# SQUID_Channel_DACS.net
KiCad netlist of a schematic drawn in Altium Designer
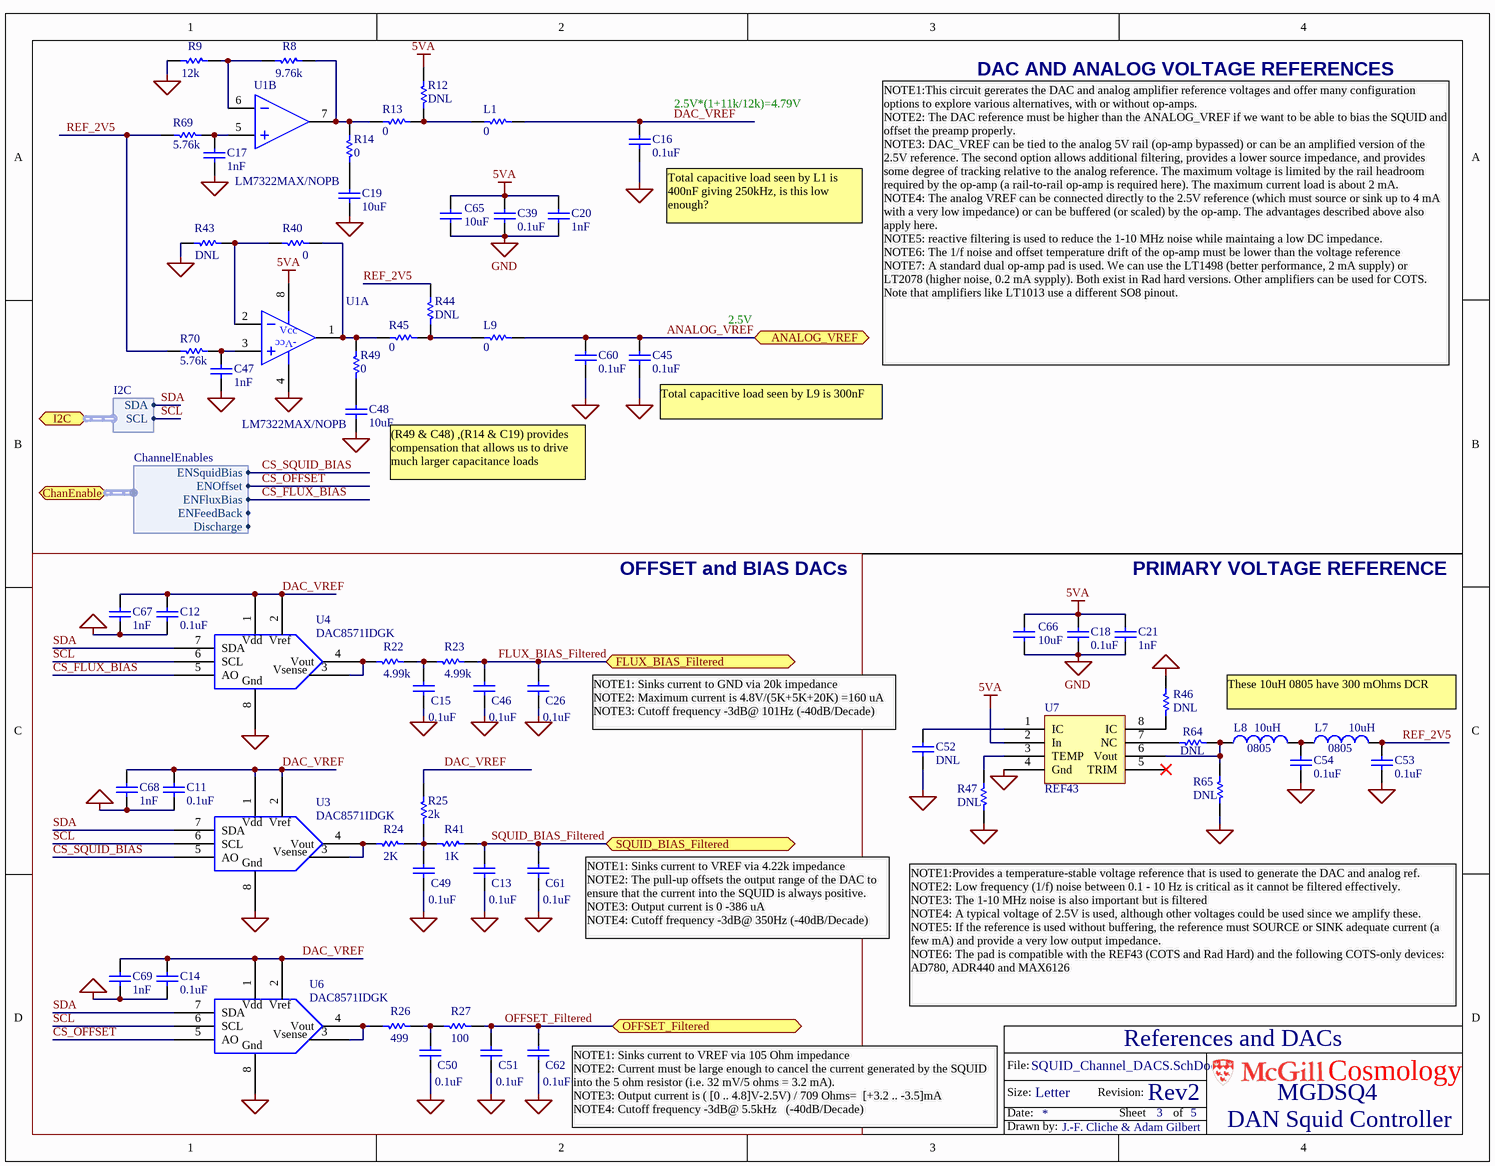
[diagram p0: SQUID_Channel_DACS.SchDoc]

(export (version "E")
  (design (tool "Eeschema 10.0.6"))
  (components
    (comp (ref "C11")
      (value "0.1uF")
      (footprint "0603")
      (description "Capacitor, Ceramic, 0603")
      (fields (field (name "MANUFACTURER") "Generic"))
      (libsource (lib "MiniSquidCtrl") (part "Cap0603"))
    )
    (comp (ref "C12")
      (value "0.1uF")
      (footprint "0603")
      (description "Capacitor, Ceramic, 0603")
      (fields (field (name "MANUFACTURER") "Generic"))
      (libsource (lib "MiniSquidCtrl") (part "Cap0603"))
    )
    (comp (ref "C13")
      (value "0.1uF")
      (footprint "0603")
      (description "Capacitor, Ceramic, 0603")
      (fields (field (name "MANUFACTURER") "Generic"))
      (libsource (lib "MiniSquidCtrl") (part "Cap0603"))
    )
    (comp (ref "C14")
      (value "0.1uF")
      (footprint "0603")
      (description "Capacitor, Ceramic, 0603")
      (fields (field (name "MANUFACTURER") "Generic"))
      (libsource (lib "MiniSquidCtrl") (part "Cap0603"))
    )
    (comp (ref "C15")
      (value "0.1uF")
      (footprint "0603")
      (description "Capacitor, Ceramic, 0603")
      (fields (field (name "MANUFACTURER") "Generic"))
      (libsource (lib "MiniSquidCtrl") (part "Cap0603"))
    )
    (comp (ref "C16")
      (value "0.1uF")
      (footprint "0603")
      (description "Capacitor, Ceramic, 0603")
      (fields (field (name "MANUFACTURER") "Generic"))
      (libsource (lib "MiniSquidCtrl") (part "Cap0603"))
    )
    (comp (ref "C17")
      (value "1nF")
      (footprint "0603")
      (description "Capacitor, Ceramic, 0603")
      (fields (field (name "MANUFACTURER") "Generic"))
      (libsource (lib "MiniSquidCtrl") (part "Cap0603"))
    )
    (comp (ref "C18")
      (value "0.1uF")
      (footprint "0603")
      (description "Capacitor, Ceramic, 0603")
      (fields (field (name "MANUFACTURER") "Generic"))
      (libsource (lib "MiniSquidCtrl") (part "Cap0603"))
    )
    (comp (ref "C19")
      (value "10uF")
      (footprint "0603")
      (description "Capacitor, Ceramic, 0603")
      (fields (field (name "MANUFACTURER") "Generic"))
      (libsource (lib "MiniSquidCtrl") (part "Cap0603"))
    )
    (comp (ref "C20")
      (value "1nF")
      (footprint "0603")
      (description "Capacitor, Ceramic, 0603")
      (fields (field (name "MANUFACTURER") "Generic"))
      (libsource (lib "MiniSquidCtrl") (part "Cap0603"))
    )
    (comp (ref "C21")
      (value "1nF")
      (footprint "0603")
      (description "Capacitor, Ceramic, 0603")
      (fields (field (name "MANUFACTURER") "Generic"))
      (libsource (lib "MiniSquidCtrl") (part "Cap0603"))
    )
    (comp (ref "C26")
      (value "0.1uF")
      (footprint "0603")
      (description "Capacitor, Ceramic, 0603")
      (fields (field (name "MANUFACTURER") "Generic"))
      (libsource (lib "MiniSquidCtrl") (part "Cap0603"))
    )
    (comp (ref "C39")
      (value "0.1uF")
      (footprint "0603")
      (description "Capacitor, Ceramic, 0603")
      (fields (field (name "MANUFACTURER") "Generic"))
      (libsource (lib "MiniSquidCtrl") (part "Cap0603"))
    )
    (comp (ref "C45")
      (value "0.1uF")
      (footprint "0603")
      (description "Capacitor, Ceramic, 0603")
      (fields (field (name "MANUFACTURER") "Generic"))
      (libsource (lib "MiniSquidCtrl") (part "Cap0603"))
    )
    (comp (ref "C46")
      (value "0.1uF")
      (footprint "0603")
      (description "Capacitor, Ceramic, 0603")
      (fields (field (name "MANUFACTURER") "Generic"))
      (libsource (lib "MiniSquidCtrl") (part "Cap0603"))
    )
    (comp (ref "C47")
      (value "1nF")
      (footprint "0603")
      (description "Capacitor, Ceramic, 0603")
      (fields (field (name "MANUFACTURER") "Generic"))
      (libsource (lib "MiniSquidCtrl") (part "Cap0603"))
    )
    (comp (ref "C48")
      (value "10uF")
      (footprint "0603")
      (description "Capacitor, Ceramic, 0603")
      (fields (field (name "MANUFACTURER") "Generic"))
      (libsource (lib "MiniSquidCtrl") (part "Cap0603"))
    )
    (comp (ref "C49")
      (value "0.1uF")
      (footprint "0603")
      (description "Capacitor, Ceramic, 0603")
      (fields (field (name "MANUFACTURER") "Generic"))
      (libsource (lib "MiniSquidCtrl") (part "Cap0603"))
    )
    (comp (ref "C50")
      (value "0.1uF")
      (footprint "0603")
      (description "Capacitor, Ceramic, 0603")
      (fields (field (name "MANUFACTURER") "Generic"))
      (libsource (lib "MiniSquidCtrl") (part "Cap0603"))
    )
    (comp (ref "C51")
      (value "0.1uF")
      (footprint "0603")
      (description "Capacitor, Ceramic, 0603")
      (fields (field (name "MANUFACTURER") "Generic"))
      (libsource (lib "MiniSquidCtrl") (part "Cap0603"))
    )
    (comp (ref "C52")
      (value "DNL")
      (footprint "0603")
      (description "Capacitor, Ceramic, 0603")
      (fields (field (name "MANUFACTURER") "Generic"))
      (libsource (lib "MiniSquidCtrl") (part "Cap0603"))
    )
    (comp (ref "C53")
      (value "0.1uF")
      (footprint "0603")
      (description "Capacitor, Ceramic, 0603")
      (fields (field (name "MANUFACTURER") "Generic"))
      (libsource (lib "MiniSquidCtrl") (part "Cap0603"))
    )
    (comp (ref "C54")
      (value "0.1uF")
      (footprint "0603")
      (description "Capacitor, Ceramic, 0603")
      (fields (field (name "MANUFACTURER") "Generic"))
      (libsource (lib "MiniSquidCtrl") (part "Cap0603"))
    )
    (comp (ref "C60")
      (value "0.1uF")
      (footprint "0603")
      (description "Capacitor, Ceramic, 0603")
      (fields (field (name "MANUFACTURER") "Generic"))
      (libsource (lib "MiniSquidCtrl") (part "Cap0603"))
    )
    (comp (ref "C61")
      (value "0.1uF")
      (footprint "0603")
      (description "Capacitor, Ceramic, 0603")
      (fields (field (name "MANUFACTURER") "Generic"))
      (libsource (lib "MiniSquidCtrl") (part "Cap0603"))
    )
    (comp (ref "C62")
      (value "0.1uF")
      (footprint "0603")
      (description "Capacitor, Ceramic, 0603")
      (fields (field (name "MANUFACTURER") "Generic"))
      (libsource (lib "MiniSquidCtrl") (part "Cap0603"))
    )
    (comp (ref "C65")
      (value "10uF")
      (footprint "CC3225-1210")
      (description "Capacitor, Ceramic, 1210")
      (fields (field (name "MANUFACTURER PART NUMBER") "1206YD106KAT2A") (field (name "VOLTAGE") "16V"))
      (libsource (lib "MiniSquidCtrl") (part "CAP 1210"))
    )
    (comp (ref "C66")
      (value "10uF")
      (footprint "CC3225-1210")
      (description "Capacitor, Ceramic, 1210")
      (fields (field (name "MANUFACTURER PART NUMBER") "1206YD106KAT2A") (field (name "VOLTAGE") "16V"))
      (libsource (lib "MiniSquidCtrl") (part "CAP 1210"))
    )
    (comp (ref "C67")
      (value "1nF")
      (footprint "0603")
      (description "Capacitor, Ceramic, 0603")
      (fields (field (name "MANUFACTURER") "Generic"))
      (libsource (lib "MiniSquidCtrl") (part "Cap0603"))
    )
    (comp (ref "C68")
      (value "1nF")
      (footprint "0603")
      (description "Capacitor, Ceramic, 0603")
      (fields (field (name "MANUFACTURER") "Generic"))
      (libsource (lib "MiniSquidCtrl") (part "Cap0603"))
    )
    (comp (ref "C69")
      (value "1nF")
      (footprint "0603")
      (description "Capacitor, Ceramic, 0603")
      (fields (field (name "MANUFACTURER") "Generic"))
      (libsource (lib "MiniSquidCtrl") (part "Cap0603"))
    )
    (comp (ref "L1")
      (value "0")
      (footprint "0603")
      (description "RES 0603")
      (fields (field (name "MANUFACTURER") "Generic"))
      (libsource (lib "MiniSquidCtrl") (part "Res0603"))
    )
    (comp (ref "L7")
      (value "10uH")
      (footprint "0805")
      (description "Inductor 0805")
      (fields (field (name "INDUCTANCE") "10uH") (field (name "MANUFACTURER") "TDK Corporation"))
      (libsource (lib "MiniSquidCtrl") (part "Inductor0603"))
    )
    (comp (ref "L8")
      (value "10uH")
      (footprint "0805")
      (description "Inductor 0805")
      (fields (field (name "INDUCTANCE") "10uH") (field (name "MANUFACTURER") "TDK Corporation"))
      (libsource (lib "MiniSquidCtrl") (part "Inductor0603"))
    )
    (comp (ref "L9")
      (value "0")
      (footprint "0603")
      (description "RES 0603")
      (fields (field (name "MANUFACTURER") "Generic"))
      (libsource (lib "MiniSquidCtrl") (part "Res0603"))
    )
    (comp (ref "R8")
      (value "9.76k")
      (footprint "0603")
      (description "RES 0603")
      (fields (field (name "MANUFACTURER") "Generic"))
      (libsource (lib "MiniSquidCtrl") (part "Res0603"))
    )
    (comp (ref "R9")
      (value "12k")
      (footprint "0603")
      (description "RES 0603")
      (fields (field (name "MANUFACTURER") "Generic"))
      (libsource (lib "MiniSquidCtrl") (part "RES 0603"))
    )
    (comp (ref "R12")
      (value "DNL")
      (footprint "0603")
      (description "RES 0603")
      (fields (field (name "MANUFACTURER") "Generic"))
      (libsource (lib "MiniSquidCtrl") (part "Res0603"))
    )
    (comp (ref "R13")
      (value "0")
      (footprint "0603")
      (description "RES 0603")
      (fields (field (name "MANUFACTURER") "Generic"))
      (libsource (lib "MiniSquidCtrl") (part "Res0603"))
    )
    (comp (ref "R14")
      (value "0")
      (footprint "0603")
      (description "RES 0603")
      (fields (field (name "MANUFACTURER") "Generic"))
      (libsource (lib "MiniSquidCtrl") (part "Res0603"))
    )
    (comp (ref "R22")
      (value "4.99k")
      (footprint "0603")
      (description "RES 0603")
      (fields (field (name "MANUFACTURER") "Generic"))
      (libsource (lib "MiniSquidCtrl") (part "Res0603"))
    )
    (comp (ref "R23")
      (value "4.99k")
      (footprint "0603")
      (description "RES 0603")
      (fields (field (name "MANUFACTURER") "Generic"))
      (libsource (lib "MiniSquidCtrl") (part "Res0603"))
    )
    (comp (ref "R24")
      (value "2K")
      (footprint "0603")
      (description "RES 0603")
      (fields (field (name "MANUFACTURER") "Generic") (field (name "Comment") "2k"))
      (libsource (lib "MiniSquidCtrl") (part "Res0603"))
    )
    (comp (ref "R25")
      (value "2k")
      (footprint "0603")
      (description "RES 0603")
      (fields (field (name "MANUFACTURER") "Generic"))
      (libsource (lib "MiniSquidCtrl") (part "Res0603"))
    )
    (comp (ref "R26")
      (value "499")
      (footprint "0603")
      (description "RES 0603")
      (fields (field (name "MANUFACTURER") "Generic"))
      (libsource (lib "MiniSquidCtrl") (part "Res0603"))
    )
    (comp (ref "R27")
      (value "100")
      (footprint "0603")
      (description "RES 0603")
      (fields (field (name "MANUFACTURER") "Generic"))
      (libsource (lib "MiniSquidCtrl") (part "Res0603"))
    )
    (comp (ref "R40")
      (value "0")
      (footprint "0603")
      (description "RES 0603")
      (fields (field (name "MANUFACTURER") "Generic"))
      (libsource (lib "MiniSquidCtrl") (part "Res0603"))
    )
    (comp (ref "R41")
      (value "1K")
      (footprint "0603")
      (description "RES 0603")
      (fields (field (name "MANUFACTURER") "Generic") (field (name "Comment") "1k"))
      (libsource (lib "MiniSquidCtrl") (part "Res0603"))
    )
    (comp (ref "R43")
      (value "DNL")
      (footprint "0603")
      (description "RES 0603")
      (fields (field (name "MANUFACTURER") "Generic"))
      (libsource (lib "MiniSquidCtrl") (part "RES 0603"))
    )
    (comp (ref "R44")
      (value "DNL")
      (footprint "0603")
      (description "RES 0603")
      (fields (field (name "MANUFACTURER") "Generic"))
      (libsource (lib "MiniSquidCtrl") (part "Res0603"))
    )
    (comp (ref "R45")
      (value "0")
      (footprint "0603")
      (description "RES 0603")
      (fields (field (name "MANUFACTURER") "Generic"))
      (libsource (lib "MiniSquidCtrl") (part "Res0603"))
    )
    (comp (ref "R46")
      (value "DNL")
      (footprint "0603")
      (description "RES 0603")
      (fields (field (name "TOLERANCE") "1%") (field (name "POWER") "1/10W"))
      (libsource (lib "MiniSquidCtrl") (part "RES 0603"))
    )
    (comp (ref "R47")
      (value "DNL")
      (footprint "0603")
      (description "RES 0603")
      (fields (field (name "MANUFACTURER") "Generic"))
      (libsource (lib "MiniSquidCtrl") (part "RES 0603"))
    )
    (comp (ref "R49")
      (value "0")
      (footprint "0603")
      (description "RES 0603")
      (fields (field (name "MANUFACTURER") "Generic"))
      (libsource (lib "MiniSquidCtrl") (part "Res0603"))
    )
    (comp (ref "R64")
      (value "DNL")
      (footprint "0603")
      (description "RES 0603")
      (fields (field (name "MANUFACTURER") "Generic"))
      (libsource (lib "MiniSquidCtrl") (part "RES 0603"))
    )
    (comp (ref "R65")
      (value "DNL")
      (footprint "0603")
      (description "RES 0603")
      (fields (field (name "MANUFACTURER") "Generic"))
      (libsource (lib "MiniSquidCtrl") (part "RES 0603"))
    )
    (comp (ref "R69")
      (value "5.76k")
      (footprint "0603")
      (description "RES 0603")
      (fields (field (name "MANUFACTURER") "Generic"))
      (libsource (lib "MiniSquidCtrl") (part "Res0603"))
    )
    (comp (ref "R70")
      (value "5.76k")
      (footprint "0603")
      (description "RES 0603")
      (fields (field (name "MANUFACTURER") "Generic"))
      (libsource (lib "MiniSquidCtrl") (part "Res0603"))
    )
    (comp (ref "U1")
      (value "LM7322MAX/NOPB")
      (footprint "SO8")
      (description "IC OP AMP DUAL 2CH LN 8-SOIC")
      (fields (field (name "MANUFACTURER") "Texas Instruments"))
      (libsource (lib "MiniSquidCtrl") (part "LMH6628"))
    )
    (comp (ref "U3")
      (value "DAC8571IDGK")
      (footprint "MSOP-8")
      (description "IC DAC 16BIT I2C V-OUT LP 8-MSOP")
      (libsource (lib "MiniSquidCtrl") (part "DAC8571IDGKR"))
    )
    (comp (ref "U4")
      (value "DAC8571IDGK")
      (footprint "MSOP-8")
      (description "IC DAC 16BIT I2C V-OUT LP 8-MSOP")
      (libsource (lib "MiniSquidCtrl") (part "DAC8571IDGKR"))
    )
    (comp (ref "U6")
      (value "DAC8571IDGK")
      (footprint "MSOP-8")
      (description "IC DAC 16BIT I2C V-OUT LP 8-MSOP")
      (libsource (lib "MiniSquidCtrl") (part "DAC8571IDGKR"))
    )
    (comp (ref "U7")
      (value "REF43")
      (footprint "SO8")
      (description "Voltage Referance")
      (libsource (lib "MiniSquidCtrl") (part "REF43"))
    )
  )
  (nets
    (net (code "3") (name "/ANALOG_VREF") (class "Default")
      (node (ref "C45") (pin "2") (pinfunction "2_2") (pintype "passive"))
      (node (ref "C60") (pin "2") (pinfunction "2_2") (pintype "passive"))
      (node (ref "L9") (pin "1") (pinfunction "1_1") (pintype "passive"))
    )
    (net (code "4") (name "/CS_FLUX_BIAS") (class "Default")
      (node (ref "U4") (pin "5") (pinfunction "AO_5") (pintype "passive"))
    )
    (net (code "5") (name "/CS_OFFSET") (class "Default")
      (node (ref "U6") (pin "5") (pinfunction "AO_5") (pintype "passive"))
    )
    (net (code "6") (name "/CS_SQUID_BIAS") (class "Default")
      (node (ref "U3") (pin "5") (pinfunction "AO_5") (pintype "passive"))
    )
    (net (code "7") (name "/DAC_VREF") (class "Default")
      (node (ref "C11") (pin "1") (pinfunction "1_1") (pintype "passive"))
      (node (ref "C12") (pin "1") (pinfunction "1_1") (pintype "passive"))
      (node (ref "C14") (pin "2") (pinfunction "2_2") (pintype "passive"))
      (node (ref "C16") (pin "2") (pinfunction "2_2") (pintype "passive"))
      (node (ref "C67") (pin "2") (pinfunction "2_2") (pintype "passive"))
      (node (ref "C68") (pin "2") (pinfunction "2_2") (pintype "passive"))
      (node (ref "C69") (pin "2") (pinfunction "2_2") (pintype "passive"))
      (node (ref "L1") (pin "1") (pinfunction "1_1") (pintype "passive"))
      (node (ref "R25") (pin "2") (pinfunction "2_2") (pintype "passive"))
      (node (ref "U3") (pin "1") (pinfunction "Vdd_1") (pintype "passive"))
      (node (ref "U3") (pin "2") (pinfunction "Vref_2") (pintype "passive"))
      (node (ref "U4") (pin "1") (pinfunction "Vdd_1") (pintype "passive"))
      (node (ref "U4") (pin "2") (pinfunction "Vref_2") (pintype "passive"))
      (node (ref "U6") (pin "1") (pinfunction "Vdd_1") (pintype "passive"))
      (node (ref "U6") (pin "2") (pinfunction "Vref_2") (pintype "passive"))
    )
    (net (code "8") (name "/FLUX_BIAS_Filtered") (class "Default")
      (node (ref "C26") (pin "1") (pinfunction "1_1") (pintype "passive"))
      (node (ref "C46") (pin "1") (pinfunction "1_1") (pintype "passive"))
      (node (ref "R23") (pin "2") (pinfunction "2_2") (pintype "passive"))
    )
    (net (code "9") (name "/OFFSET_Filtered") (class "Default")
      (node (ref "C51") (pin "1") (pinfunction "1_1") (pintype "passive"))
      (node (ref "C62") (pin "1") (pinfunction "1_1") (pintype "passive"))
      (node (ref "R27") (pin "2") (pinfunction "2_2") (pintype "passive"))
    )
    (net (code "10") (name "/REF_2V5") (class "Default")
      (node (ref "C53") (pin "2") (pinfunction "2_2") (pintype "passive"))
      (node (ref "L7") (pin "1") (pinfunction "1_1") (pintype "passive"))
      (node (ref "R44") (pin "1") (pinfunction "1_1") (pintype "passive"))
      (node (ref "R69") (pin "2") (pinfunction "2_2") (pintype "passive"))
      (node (ref "R70") (pin "2") (pinfunction "2_2") (pintype "passive"))
    )
    (net (code "11") (name "/SCL") (class "Default")
      (node (ref "U3") (pin "6") (pinfunction "SCL_6") (pintype "passive"))
      (node (ref "U4") (pin "6") (pinfunction "SCL_6") (pintype "passive"))
      (node (ref "U6") (pin "6") (pinfunction "SCL_6") (pintype "passive"))
    )
    (net (code "12") (name "/SDA") (class "Default")
      (node (ref "U3") (pin "7") (pinfunction "SDA_7") (pintype "passive"))
      (node (ref "U4") (pin "7") (pinfunction "SDA_7") (pintype "passive"))
      (node (ref "U6") (pin "7") (pinfunction "SDA_7") (pintype "passive"))
    )
    (net (code "13") (name "/SQUID_BIAS_Filtered") (class "Default")
      (node (ref "C13") (pin "1") (pinfunction "1_1") (pintype "passive"))
      (node (ref "C61") (pin "1") (pinfunction "1_1") (pintype "passive"))
      (node (ref "R41") (pin "2") (pinfunction "2_2") (pintype "passive"))
    )
    (net (code "16") (name "5VA") (class "Default")
      (node (ref "C18") (pin "2") (pinfunction "2_2") (pintype "passive"))
      (node (ref "C20") (pin "2") (pinfunction "2_2") (pintype "passive"))
      (node (ref "C21") (pin "2") (pinfunction "2_2") (pintype "passive"))
      (node (ref "C39") (pin "2") (pinfunction "2_2") (pintype "passive"))
      (node (ref "C65") (pin "2") (pinfunction "2_2") (pintype "passive"))
      (node (ref "C66") (pin "2") (pinfunction "2_2") (pintype "passive"))
      (node (ref "R12") (pin "1") (pinfunction "1_1") (pintype "passive"))
      (node (ref "U1") (pin "8") (pinfunction "VDD_8") (pintype "passive"))
      (node (ref "U7") (pin "2") (pinfunction "In_2") (pintype "passive"))
    )
    (net (code "17") (name "GND") (class "Default")
      (node (ref "C11") (pin "2") (pinfunction "2_2") (pintype "passive"))
      (node (ref "C12") (pin "2") (pinfunction "2_2") (pintype "passive"))
      (node (ref "C13") (pin "2") (pinfunction "2_2") (pintype "passive"))
      (node (ref "C14") (pin "1") (pinfunction "1_1") (pintype "passive"))
      (node (ref "C15") (pin "2") (pinfunction "2_2") (pintype "passive"))
      (node (ref "C16") (pin "1") (pinfunction "1_1") (pintype "passive"))
      (node (ref "C17") (pin "1") (pinfunction "1_1") (pintype "passive"))
      (node (ref "C18") (pin "1") (pinfunction "1_1") (pintype "passive"))
      (node (ref "C19") (pin "1") (pinfunction "1_1") (pintype "passive"))
      (node (ref "C20") (pin "1") (pinfunction "1_1") (pintype "passive"))
      (node (ref "C21") (pin "1") (pinfunction "1_1") (pintype "passive"))
      (node (ref "C26") (pin "2") (pinfunction "2_2") (pintype "passive"))
      (node (ref "C39") (pin "1") (pinfunction "1_1") (pintype "passive"))
      (node (ref "C45") (pin "1") (pinfunction "1_1") (pintype "passive"))
      (node (ref "C46") (pin "2") (pinfunction "2_2") (pintype "passive"))
      (node (ref "C47") (pin "1") (pinfunction "1_1") (pintype "passive"))
      (node (ref "C48") (pin "1") (pinfunction "1_1") (pintype "passive"))
      (node (ref "C49") (pin "2") (pinfunction "2_2") (pintype "passive"))
      (node (ref "C50") (pin "2") (pinfunction "2_2") (pintype "passive"))
      (node (ref "C51") (pin "2") (pinfunction "2_2") (pintype "passive"))
      (node (ref "C52") (pin "1") (pinfunction "1_1") (pintype "passive"))
      (node (ref "C53") (pin "1") (pinfunction "1_1") (pintype "passive"))
      (node (ref "C54") (pin "1") (pinfunction "1_1") (pintype "passive"))
      (node (ref "C60") (pin "1") (pinfunction "1_1") (pintype "passive"))
      (node (ref "C61") (pin "2") (pinfunction "2_2") (pintype "passive"))
      (node (ref "C62") (pin "2") (pinfunction "2_2") (pintype "passive"))
      (node (ref "C65") (pin "1") (pinfunction "1_1") (pintype "passive"))
      (node (ref "C66") (pin "1") (pinfunction "1_1") (pintype "passive"))
      (node (ref "C67") (pin "1") (pinfunction "1_1") (pintype "passive"))
      (node (ref "C68") (pin "1") (pinfunction "1_1") (pintype "passive"))
      (node (ref "C69") (pin "1") (pinfunction "1_1") (pintype "passive"))
      (node (ref "R43") (pin "2") (pinfunction "2_2") (pintype "passive"))
      (node (ref "R46") (pin "2") (pinfunction "2_2") (pintype "passive"))
      (node (ref "R47") (pin "1") (pinfunction "1_1") (pintype "passive"))
      (node (ref "R65") (pin "1") (pinfunction "1_1") (pintype "passive"))
      (node (ref "R9") (pin "2") (pinfunction "2_2") (pintype "passive"))
      (node (ref "U1") (pin "4") (pinfunction "GND_4") (pintype "passive"))
      (node (ref "U3") (pin "8") (pinfunction "Gnd_8") (pintype "passive"))
      (node (ref "U4") (pin "8") (pinfunction "Gnd_8") (pintype "passive"))
      (node (ref "U6") (pin "8") (pinfunction "Gnd_8") (pintype "passive"))
      (node (ref "U7") (pin "4") (pinfunction "Gnd_4") (pintype "passive"))
    )
    (net (code "18") (name "Net-(C15-Pad1)") (class "Default")
      (node (ref "C15") (pin "1") (pinfunction "1_1") (pintype "passive"))
      (node (ref "R22") (pin "2") (pinfunction "2_2") (pintype "passive"))
      (node (ref "R23") (pin "1") (pinfunction "1_1") (pintype "passive"))
    )
    (net (code "19") (name "Net-(C19-Pad2)") (class "Default")
      (node (ref "C19") (pin "2") (pinfunction "2_2") (pintype "passive"))
      (node (ref "R14") (pin "2") (pinfunction "2_2") (pintype "passive"))
    )
    (net (code "20") (name "Net-(C48-Pad2)") (class "Default")
      (node (ref "C48") (pin "2") (pinfunction "2_2") (pintype "passive"))
      (node (ref "R49") (pin "2") (pinfunction "2_2") (pintype "passive"))
    )
    (net (code "21") (name "Net-(C49-Pad1)") (class "Default")
      (node (ref "C49") (pin "1") (pinfunction "1_1") (pintype "passive"))
      (node (ref "R24") (pin "2") (pinfunction "2_2") (pintype "passive"))
      (node (ref "R25") (pin "1") (pinfunction "1_1") (pintype "passive"))
      (node (ref "R41") (pin "1") (pinfunction "1_1") (pintype "passive"))
    )
    (net (code "22") (name "Net-(C50-Pad1)") (class "Default")
      (node (ref "C50") (pin "1") (pinfunction "1_1") (pintype "passive"))
      (node (ref "R26") (pin "2") (pinfunction "2_2") (pintype "passive"))
      (node (ref "R27") (pin "1") (pinfunction "1_1") (pintype "passive"))
    )
    (net (code "23") (name "Net-(C52-Pad2)") (class "Default")
      (node (ref "C52") (pin "2") (pinfunction "2_2") (pintype "passive"))
      (node (ref "U7") (pin "1") (pinfunction "IC_1") (pintype "passive"))
    )
    (net (code "24") (name "Net-(C54-Pad2)") (class "Default")
      (node (ref "C54") (pin "2") (pinfunction "2_2") (pintype "passive"))
      (node (ref "L7") (pin "2") (pinfunction "2_2") (pintype "passive"))
      (node (ref "L8") (pin "1") (pinfunction "1_1") (pintype "passive"))
    )
    (net (code "25") (name "Net-(L1-Pad2)") (class "Default")
      (node (ref "L1") (pin "2") (pinfunction "2_2") (pintype "passive"))
      (node (ref "R12") (pin "2") (pinfunction "2_2") (pintype "passive"))
      (node (ref "R13") (pin "2") (pinfunction "2_2") (pintype "passive"))
    )
    (net (code "26") (name "Net-(L9-Pad2)") (class "Default")
      (node (ref "L9") (pin "2") (pinfunction "2_2") (pintype "passive"))
      (node (ref "R44") (pin "2") (pinfunction "2_2") (pintype "passive"))
      (node (ref "R45") (pin "2") (pinfunction "2_2") (pintype "passive"))
    )
    (net (code "27") (name "Net-(R46-Pad1)") (class "Default")
      (node (ref "R46") (pin "1") (pinfunction "1_1") (pintype "passive"))
      (node (ref "U7") (pin "8") (pinfunction "IC_8") (pintype "passive"))
    )
    (net (code "28") (name "Net-(U1A-IN+)") (class "Default")
      (node (ref "C47") (pin "2") (pinfunction "2_2") (pintype "passive"))
      (node (ref "R70") (pin "1") (pinfunction "1_1") (pintype "passive"))
      (node (ref "U1") (pin "3") (pinfunction "IN+_3") (pintype "passive"))
    )
    (net (code "29") (name "Net-(U1A-IN-)") (class "Default")
      (node (ref "R40") (pin "1") (pinfunction "1_1") (pintype "passive"))
      (node (ref "R43") (pin "1") (pinfunction "1_1") (pintype "passive"))
      (node (ref "U1") (pin "2") (pinfunction "IN-_2") (pintype "passive"))
    )
    (net (code "30") (name "Net-(U1A-OUT)") (class "Default")
      (node (ref "R40") (pin "2") (pinfunction "2_2") (pintype "passive"))
      (node (ref "R45") (pin "1") (pinfunction "1_1") (pintype "passive"))
      (node (ref "R49") (pin "1") (pinfunction "1_1") (pintype "passive"))
      (node (ref "U1") (pin "1") (pinfunction "OUT_1") (pintype "passive"))
    )
    (net (code "31") (name "Net-(U1B-IN+)") (class "Default")
      (node (ref "C17") (pin "2") (pinfunction "2_2") (pintype "passive"))
      (node (ref "R69") (pin "1") (pinfunction "1_1") (pintype "passive"))
      (node (ref "U1") (pin "5") (pinfunction "IN+_5") (pintype "passive"))
    )
    (net (code "32") (name "Net-(U1B-IN-)") (class "Default")
      (node (ref "R8") (pin "1") (pinfunction "1_1") (pintype "passive"))
      (node (ref "R9") (pin "1") (pinfunction "1_1") (pintype "passive"))
      (node (ref "U1") (pin "6") (pinfunction "IN-_6") (pintype "passive"))
    )
    (net (code "33") (name "Net-(U1B-OUT)") (class "Default")
      (node (ref "R13") (pin "1") (pinfunction "1_1") (pintype "passive"))
      (node (ref "R14") (pin "1") (pinfunction "1_1") (pintype "passive"))
      (node (ref "R8") (pin "2") (pinfunction "2_2") (pintype "passive"))
      (node (ref "U1") (pin "7") (pinfunction "OUT_7") (pintype "passive"))
    )
    (net (code "34") (name "Net-(U3-Vout)") (class "Default")
      (node (ref "R24") (pin "1") (pinfunction "1_1") (pintype "passive"))
      (node (ref "U3") (pin "3") (pinfunction "Vsense_3") (pintype "passive"))
      (node (ref "U3") (pin "4") (pinfunction "Vout_4") (pintype "passive"))
    )
    (net (code "35") (name "Net-(U4-Vout)") (class "Default")
      (node (ref "R22") (pin "1") (pinfunction "1_1") (pintype "passive"))
      (node (ref "U4") (pin "3") (pinfunction "Vsense_3") (pintype "passive"))
      (node (ref "U4") (pin "4") (pinfunction "Vout_4") (pintype "passive"))
    )
    (net (code "36") (name "Net-(U6-Vout)") (class "Default")
      (node (ref "R26") (pin "1") (pinfunction "1_1") (pintype "passive"))
      (node (ref "U6") (pin "3") (pinfunction "Vsense_3") (pintype "passive"))
      (node (ref "U6") (pin "4") (pinfunction "Vout_4") (pintype "passive"))
    )
    (net (code "37") (name "Net-(U7-NC)") (class "Default")
      (node (ref "R64") (pin "2") (pinfunction "2_2") (pintype "passive"))
      (node (ref "U7") (pin "7") (pinfunction "NC_7") (pintype "passive"))
    )
    (net (code "38") (name "Net-(U7-TEMP)") (class "Default")
      (node (ref "R47") (pin "2") (pinfunction "2_2") (pintype "passive"))
      (node (ref "U7") (pin "3") (pinfunction "TEMP_3") (pintype "passive"))
    )
    (net (code "39") (name "Net-(U7-Vout)") (class "Default")
      (node (ref "L8") (pin "2") (pinfunction "2_2") (pintype "passive"))
      (node (ref "R64") (pin "1") (pinfunction "1_1") (pintype "passive"))
      (node (ref "R65") (pin "2") (pinfunction "2_2") (pintype "passive"))
      (node (ref "U7") (pin "6") (pinfunction "Vout_6") (pintype "passive"))
    )
    (net (code "40") (name "unconnected-(U7-TRIM-Pad5)") (class "Default")
      (node (ref "U7") (pin "5") (pinfunction "TRIM_5") (pintype "passive+no_connect"))
    )
  )
)
